# 3_4_4_2V_TO_FIXED_3_3V.net
KiCad netlist of a schematic drawn in Altium Designer
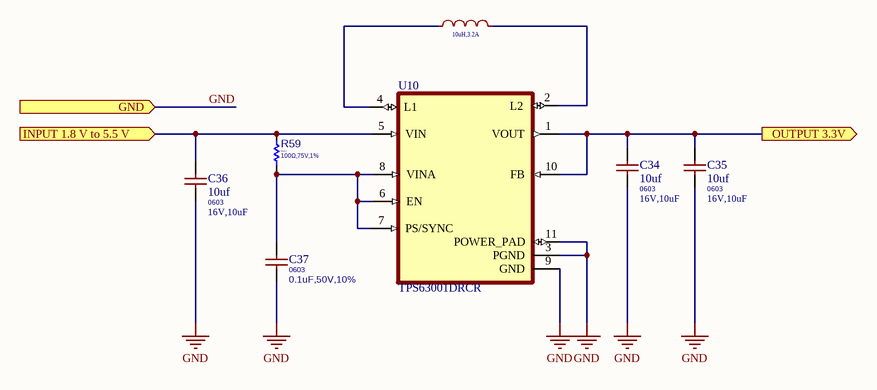
[diagram p0: 3.4_4.2V_TO_FIXED_3.3V.SchDoc]

(export (version "E")
  (design (tool "Eeschema 10.0.6"))
  (components
    (comp (ref "C34")
      (value "10uf")
      (footprint "CAPC1608X90N")
      (description "16V 10uF Y5V ±20% 0603 Multilayer Ceramic Capacitors MLCC - SMD/SMT ROHS")
      (fields
        (field (name "MANUFACTURER") "KEMET")
        (field (name "MPN") "CC0603KRX7R9BB104")
        (field (name "PACKAGE") "0603")
        (field (name "ALTIUM_VALUE") "16V,10uF")
      )
      (libsource (lib "RCL") (part "0603F106M160NT"))
    )
    (comp (ref "C35")
      (value "10uf")
      (footprint "CAPC1608X90N")
      (description "16V 10uF Y5V ±20% 0603 Multilayer Ceramic Capacitors MLCC - SMD/SMT ROHS")
      (fields
        (field (name "MANUFACTURER") "KEMET")
        (field (name "MPN") "CC0603KRX7R9BB104")
        (field (name "PACKAGE") "0603")
        (field (name "ALTIUM_VALUE") "16V,10uF")
      )
      (libsource (lib "RCL") (part "0603F106M160NT"))
    )
    (comp (ref "C36")
      (value "10uf")
      (footprint "CAPC1608X90N")
      (description "16V 10uF Y5V ±20% 0603 Multilayer Ceramic Capacitors MLCC - SMD/SMT ROHS")
      (fields
        (field (name "MANUFACTURER") "KEMET")
        (field (name "MPN") "CC0603KRX7R9BB104")
        (field (name "PACKAGE") "0603")
        (field (name "ALTIUM_VALUE") "16V,10uF")
      )
      (libsource (lib "RCL") (part "0603F106M160NT"))
    )
    (comp (ref "C37")
      (value "0.1uF,50V,10%")
      (footprint "C0603")
      (description "CAP CER 0.1UF 50V X7R 0603")
      (fields
        (field (name "MANUFACTURER") "Murata Electronics")
        (field (name "MPN") "GCM188R71H104KA57J")
        (field (name "PACKAGE") "0603")
      )
      (libsource (lib "RCL") (part "GCM188R71H104KA57J"))
    )
    (comp (ref "L1")
      (value "10uH,3.2A")
      (footprint "inductor_SMD,5.2x5.4mm")
      (description "3.2A 10uH Integrated molded inductor ±20% 3.5A SMD,5.2x5.4mm Power Inductors ROHS")
      (fields (field (name "MANUFACTURER") "cjiang") (field (name "MPN") "FXL0530-100-M"))
      (libsource (lib "RCL") (part "FXL0530-100-M"))
    )
    (comp (ref "R59")
      (value "100Ω,75V,1%")
      (footprint "R0603")
      (description "100mW Thick Film Resistors 75V ±100ppm/℃ ±1% 100Ω 0603 Chip Resistor - Surface Mount ROHS")
      (fields
        (field (name "MANUFACTURER") "YAGEO(国巨)")
        (field (name "MPN") "AC0603FR-13100RL")
        (field (name "PACKAGE") "0603")
      )
      (libsource (lib "RCL") (part "AC0603FR-13100RL"))
    )
    (comp (ref "U10")
      (value "TPS63001DRCR")
      (footprint "IC:VREG_V62/16624-01YE")
      (fields (field (name "MF") "Texas Instruments"))
      (libsource (lib "IC") (part "TPS63001DRCR"))
    )
  )
  (nets
    (net (code "1") (name "/INPUT 1.8 V to 5.5 V") (class "Default")
      (node (ref "C36") (pin "2") (pinfunction "2_2") (pintype "passive"))
      (node (ref "R59") (pin "2") (pinfunction "2_2") (pintype "passive"))
      (node (ref "U10") (pin "5") (pinfunction "VIN_5") (pintype "input"))
    )
    (net (code "2") (name "/OUTPUT 3.3V") (class "Default")
      (node (ref "C34") (pin "2") (pinfunction "2_2") (pintype "passive"))
      (node (ref "C35") (pin "2") (pinfunction "2_2") (pintype "passive"))
      (node (ref "U10") (pin "1") (pinfunction "VOUT_1") (pintype "output"))
      (node (ref "U10") (pin "10") (pinfunction "FB_10") (pintype "input"))
    )
    (net (code "3") (name "GND") (class "Default")
      (node (ref "C34") (pin "1") (pinfunction "1_1") (pintype "passive"))
      (node (ref "C35") (pin "1") (pinfunction "1_1") (pintype "passive"))
      (node (ref "C36") (pin "1") (pinfunction "1_1") (pintype "passive"))
      (node (ref "C37") (pin "1") (pinfunction "1_1") (pintype "passive"))
      (node (ref "U10") (pin "11") (pinfunction "POWER_PAD_11") (pintype "bidirectional"))
      (node (ref "U10") (pin "3") (pinfunction "PGND_3") (pintype "power_in"))
      (node (ref "U10") (pin "9") (pinfunction "GND_9") (pintype "power_in"))
    )
    (net (code "4") (name "Net-(U10-EN)") (class "Default")
      (node (ref "C37") (pin "2") (pinfunction "2_2") (pintype "passive"))
      (node (ref "R59") (pin "1") (pinfunction "1_1") (pintype "passive"))
      (node (ref "U10") (pin "6") (pinfunction "EN_6") (pintype "input"))
      (node (ref "U10") (pin "7") (pinfunction "PS/SYNC_7") (pintype "input"))
      (node (ref "U10") (pin "8") (pinfunction "VINA_8") (pintype "input"))
    )
    (net (code "5") (name "Net-(U10-L1)") (class "Default")
      (node (ref "L1") (pin "1") (pinfunction "1_1") (pintype "passive"))
      (node (ref "U10") (pin "4") (pinfunction "L1_4") (pintype "bidirectional"))
    )
    (net (code "6") (name "Net-(U10-L2)") (class "Default")
      (node (ref "L1") (pin "2") (pinfunction "2_2") (pintype "passive"))
      (node (ref "U10") (pin "2") (pinfunction "L2_2") (pintype "bidirectional"))
    )
  )
)
